# FRU_Programmer.net
KiCad netlist of a schematic drawn in Altium Designer
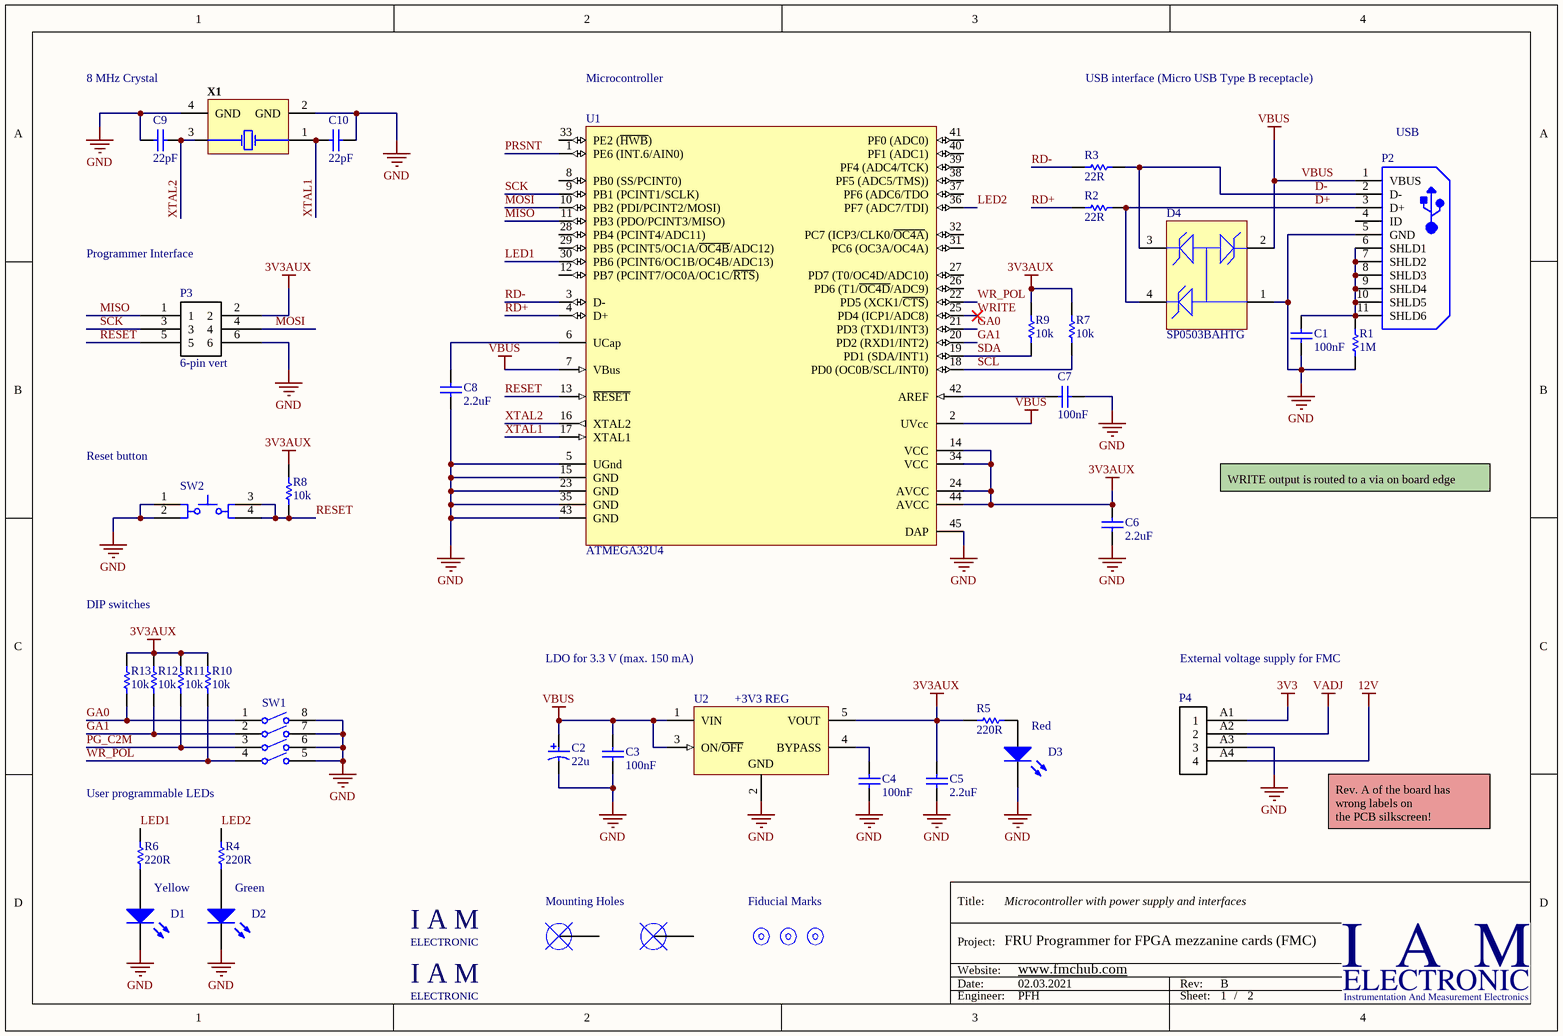
[diagram p0: FRU_Programmer.SchDoc]

(export (version "E")
  (design (tool "Eeschema 10.0.6"))
  (components
    (comp (ref "C1")
      (value "100nF")
      (footprint "CAPC0603(1608)100_L")
      (description "CAP 100nF, 0603 (1608 Metric)")
      (fields (field (name "TOLERANCE") "Â±5%") (field (name "PART") "C0603C104M4RAC7411"))
      (libsource (lib "Altium Content Vault") (part "CAP"))
    )
    (comp (ref "C2")
      (value "22u")
      (footprint "AVX-TAJ-B-2_L")
      (description "Standard Tantalum, 22 uF, +/- 10%, 16 V, -55 to 125 degC, 2-Pin SMD (1210), RoHS, Tape and Reel")
      (fields (field (name "TOLERANCE") "10%") (field (name "MANUFACTURER") "AVX"))
      (libsource (lib "Altium Content Vault") (part "CAP-P-2"))
    )
    (comp (ref "C3")
      (value "100nF")
      (footprint "CAPC0603(1608)100_L")
      (description "CAP 100nF, 0603 (1608 Metric)")
      (fields (field (name "TOLERANCE") "Â±5%") (field (name "PART") "C0603C104M4RAC7411"))
      (libsource (lib "Altium Content Vault") (part "CAP"))
    )
    (comp (ref "C4")
      (value "100nF")
      (footprint "CAPC0603(1608)100_L")
      (description "CAP 100nF, 0603 (1608 Metric)")
      (fields (field (name "TOLERANCE") "Â±5%") (field (name "MANUFACTURER") "KEMET"))
      (libsource (lib "Altium Content Vault") (part "CAP"))
    )
    (comp (ref "C5")
      (value "2.2uF")
      (footprint "CAPC0603(1608)100_L")
      (description "CAP 2.2uF, 0603 (1608 Metric)")
      (fields (field (name "TOLERANCE") "Â±5%") (field (name "PART") "C0603C225K4PACTU"))
      (libsource (lib "Altium Content Vault") (part "CAP"))
    )
    (comp (ref "C6")
      (value "2.2uF")
      (footprint "CAPC0603(1608)100_L")
      (description "CAP 2.2uF, 0603 (1608 Metric)")
      (fields (field (name "TOLERANCE") "Â±5%") (field (name "PART") "C0603C225K4PACTU"))
      (libsource (lib "Altium Content Vault") (part "CAP"))
    )
    (comp (ref "C7")
      (value "100nF")
      (footprint "CAPC0603(1608)100_L")
      (description "CAP 100nF, 0603 (1608 Metric)")
      (fields (field (name "TOLERANCE") "Â±5%") (field (name "PART") "C0603C104M4RAC7411"))
      (libsource (lib "Altium Content Vault") (part "CAP"))
    )
    (comp (ref "C8")
      (value "2.2uF")
      (footprint "CAPC0603(1608)100_L")
      (description "CAP 2.2uF, 0603 (1608 Metric)")
      (fields (field (name "TOLERANCE") "Â±5%") (field (name "MANUFACTURER") "KEMET"))
      (libsource (lib "Altium Content Vault") (part "CAP"))
    )
    (comp (ref "C9")
      (value "22pF")
      (footprint "CAPC0603(1608)100_L")
      (description "CAP 22pF, 0603 (1608 Metric)")
      (fields (field (name "TOLERANCE") "Â±5%") (field (name "PART") "CC0603JRNPO9BN220"))
      (libsource (lib "Altium Content Vault") (part "CAP"))
    )
    (comp (ref "C10")
      (value "22pF")
      (footprint "CAPC0603(1608)100_L")
      (description "CAP 22pF, 0603 (1608 Metric)")
      (fields (field (name "TOLERANCE") "Â±5%") (field (name "PART") "CC0603JRNPO9BN220"))
      (libsource (lib "Altium Content Vault") (part "CAP"))
    )
    (comp (ref "D1")
      (value "LED Yellow")
      (footprint "0603_A")
      (description "LED 0603, 2V, Yellow")
      (fields (field (name "PARTNUMBER") "150060YS75000") (field (name "MANUFACTURER") "Wuerth Elektronik"))
      (libsource (lib "Altium Content Vault") (part "WE-LED_K1A2-2"))
    )
    (comp (ref "D2")
      (value "LED Green")
      (footprint "0603_A")
      (description "LED 0603, 2V, Green")
      (fields (field (name "PARTNUMBER") "150060VS75000") (field (name "MANUFACTURER") "Wuerth Elektronik"))
      (libsource (lib "Altium Content Vault") (part "WE-LED_K1A2-2"))
    )
    (comp (ref "D3")
      (value "LED Red")
      (footprint "0603_A")
      (description "LED 0603, 2V, Red")
      (fields (field (name "PARTNUMBER") "150060RS75000") (field (name "MANUFACTURER") "Wuerth Elektronik"))
      (libsource (lib "Altium Content Vault") (part "WE-LED_K1A2-2"))
    )
    (comp (ref "D4")
      (value "SP0503BAHTG")
      (footprint "LFUS-SOT143-4_V")
      (description "TVS Diode Array, 30 pF, 30 KV, -40 to 85 degC, 4-Pin SOT143, RoHS, Tape and Reel")
      (fields (field (name "MANUFACTURER") "Littelfuse"))
      (libsource (lib "Altium Content Vault") (part "LFUS-SP0503BAHTG-SOT143-4"))
    )
    (comp (ref "FM1")
      (value "1mm")
      (footprint "FIDUCIAL_MARK_ROUND_RING")
      (description "Fiducial mark, width 1mm, clearance 3mm")
      (libsource (lib "VITA_57_FMC") (part "Fiducial_Mark"))
    )
    (comp (ref "FM2")
      (value "1mm")
      (footprint "FIDUCIAL_MARK_ROUND_RING")
      (description "Fiducial mark, width 1mm, clearance 3mm")
      (libsource (lib "VITA_57_FMC") (part "Fiducial_Mark"))
    )
    (comp (ref "FM3")
      (value "1mm")
      (footprint "FIDUCIAL_MARK_ROUND_RING")
      (description "Fiducial mark, width 1mm, clearance 3mm")
      (libsource (lib "VITA_57_FMC") (part "Fiducial_Mark"))
    )
    (comp (ref "MH1")
      (value "2.7mm")
      (footprint "Mounting_Hole_Plated_2.7mm-COVERED")
      (description "Mounting hole, hole size 2.7mm")
      (libsource (lib "VITA_57_FMC") (part "Mounting_Hole_2.7mm"))
    )
    (comp (ref "MH2")
      (value "2.7mm")
      (footprint "Mounting_Hole_Plated_2.7mm-COVERED")
      (description "Mounting hole, hole size 2.7mm")
      (libsource (lib "VITA_57_FMC") (part "Mounting_Hole_2.7mm"))
    )
    (comp (ref "P2")
      (value "USB Jack")
      (footprint "FCI-10118193-0001LF-5_V")
      (description "Micro USB B Type Receptacle, -55 to 85 degC, 5-Pin SMD, RoHS, Tape and Reel")
      (fields (field (name "MANUFACTURER") "FCI") (field (name "PART") "10118193-0001LF"))
      (libsource (lib "Altium Content Vault") (part "USB-5-6SHLD"))
    )
    (comp (ref "P3")
      (value "6-pin vert")
      (footprint "TSM-103-01-T-DV")
      (description ".100\" (2.54 mm) pitch 6 pin (dual row) header, 0.38\" (9.65 mm) total height, SMT")
      (fields (field (name "MANUFACTURER") "Samtec") (field (name "PART") "TSM-103-01-T-DV"))
      (libsource (lib "SMTC-TSM") (part "TSM-103-01-T-DV"))
    )
    (comp (ref "P4")
      (value "PTSM SMT connector")
      (footprint "PTSM-4pol")
      (description "Phoenix Contact PTSM SMT connector")
      (fields (field (name "MANUFACTURER") "Phoenix Contact") (field (name "PART") "1814650"))
      (libsource (lib "PC-PTSM") (part "PC-PTSM-4pol"))
    )
    (comp (ref "R1")
      (value "1M")
      (footprint "RESC1608X55X25NL10T15")
      (description "Resistor, 1 MOhm, 0603 (1608 Metric)")
      (fields (field (name "MANUFACTURER") "Yageo") (field (name "TOLERANCE") "5%"))
      (libsource (lib "Altium Content Vault") (part "RES-2"))
    )
    (comp (ref "R2")
      (value "22R")
      (footprint "RESC0603(1608)_L")
      (description "22R 0.1W 5% 0603 (1608 Metric)  SMD")
      (fields (field (name "POWER") "0.1 W") (field (name "TOLERANCE") "5 %"))
      (libsource (lib "Altium Content Vault") (part "CMP-1012-00034-1"))
    )
    (comp (ref "R3")
      (value "22R")
      (footprint "RESC0603(1608)_L")
      (description "22R 0.1W 5% 0603 (1608 Metric)  SMD")
      (fields (field (name "POWER") "0.1 W") (field (name "TOLERANCE") "5 %"))
      (libsource (lib "Altium Content Vault") (part "CMP-1012-00034-1"))
    )
    (comp (ref "R4")
      (value "220R")
      (footprint "RESC1608X55X25NL10T15")
      (description "Resistors, 220 Ohm, +/- 1%, 0603 (1608 Metric)")
      (fields (field (name "PART") "RC0603FR-07220RL") (field (name "MANUFACTURER") "Yageo"))
      (libsource (lib "Altium Content Vault") (part "RES-2"))
    )
    (comp (ref "R5")
      (value "220R")
      (footprint "RESC1608X55X25NL10T15")
      (description "Resistors, 220 Ohm, +/- 1%, 0603 (1608 Metric)")
      (fields (field (name "PART") "RC0603FR-07220RL") (field (name "MANUFACTURER") "Yageo"))
      (libsource (lib "Altium Content Vault") (part "RES-2"))
    )
    (comp (ref "R6")
      (value "220R")
      (footprint "RESC1608X55X25NL10T15")
      (description "Resistors, 220 Ohm, +/- 1%, 0603 (1608 Metric)")
      (fields (field (name "PART") "RC0603FR-07220RL") (field (name "MANUFACTURER") "Yageo"))
      (libsource (lib "Altium Content Vault") (part "RES-2"))
    )
    (comp (ref "R7")
      (value "10k")
      (footprint "RESC1608X55X25NL10T15")
      (description "Resistor, 10 KOhm, 0603 (1608 Metric)")
      (fields (field (name "MANUFACTURER") "Walsin") (field (name "TOLERANCE") "5%"))
      (libsource (lib "Altium Content Vault") (part "RES-2"))
    )
    (comp (ref "R8")
      (value "10k")
      (footprint "RESC1608X55X25NL10T15")
      (description "Resistor, 10 KOhm, 0603 (1608 Metric)")
      (fields (field (name "MANUFACTURER") "Walsin") (field (name "TOLERANCE") "5%"))
      (libsource (lib "Altium Content Vault") (part "RES-2"))
    )
    (comp (ref "R9")
      (value "10k")
      (footprint "RESC1608X55X25NL10T15")
      (description "Resistor, 10 KOhm, 0603 (1608 Metric)")
      (fields (field (name "MANUFACTURER") "Walsin") (field (name "TOLERANCE") "5%"))
      (libsource (lib "Altium Content Vault") (part "RES-2"))
    )
    (comp (ref "R10")
      (value "10k")
      (footprint "RESC1608X55X25NL10T15")
      (description "Resistor, 10 KOhm, 0603 (1608 Metric)")
      (fields (field (name "MANUFACTURER") "Walsin") (field (name "TOLERANCE") "5%"))
      (libsource (lib "Altium Content Vault") (part "RES-2"))
    )
    (comp (ref "R11")
      (value "10k")
      (footprint "RESC1608X55X25NL10T15")
      (description "Resistor, 10 KOhm, 0603 (1608 Metric)")
      (fields (field (name "MANUFACTURER") "Walsin") (field (name "TOLERANCE") "5%"))
      (libsource (lib "Altium Content Vault") (part "RES-2"))
    )
    (comp (ref "R12")
      (value "10k")
      (footprint "RESC1608X55X25NL10T15")
      (description "Resistor, 10 KOhm, 0603 (1608 Metric)")
      (fields (field (name "MANUFACTURER") "Walsin") (field (name "TOLERANCE") "5%"))
      (libsource (lib "Altium Content Vault") (part "RES-2"))
    )
    (comp (ref "R13")
      (value "10k")
      (footprint "RESC1608X55X25NL10T15")
      (description "Resistor, 10 KOhm, 0603 (1608 Metric)")
      (fields (field (name "MANUFACTURER") "Walsin") (field (name "TOLERANCE") "5%"))
      (libsource (lib "Altium Content Vault") (part "RES-2"))
    )
    (comp (ref "STR1")
      (value "IAM LOGO")
      (footprint "IAM LOGO - MEDIUM - WWW")
      (description "I A M E L E C T R O N I C - Logo")
      (fields (field (name "MANUFACTURER") "IAM ELECTRONIC") (field (name "PART") "Logo"))
      (libsource (lib "IAM_LOGOS") (part "IAM_LOGO"))
    )
    (comp (ref "STR2")
      (value "IAM LOGO")
      (footprint "IAM LOGO - LARGE - WWW")
      (description "I A M E L E C T R O N I C - Logo")
      (fields (field (name "MANUFACTURER") "IAM ELECTRONIC") (field (name "PART") "Logo"))
      (libsource (lib "IAM_LOGOS") (part "IAM_LOGO"))
    )
    (comp (ref "SW1")
      (value "DIP switch")
      (footprint "218-4LPST")
      (description "4 channel DIP switch")
      (fields (field (name "MANUFACTURER") "CTS Electronic Components") (field (name "PART") "218-4LPST"))
      (libsource (lib "CTS-218") (part "218-4LPST"))
    )
    (comp (ref "SW2")
      (value "Push switch")
      (footprint "ESWI-TL3342F160QG_V")
      (description "Switch, Tactile, SPST-NO, 50 mA, 12 V, 4-Pin SMD, RoHS, Tape and Reel")
      (fields (field (name "TOLERANCE") "20%") (field (name "PART") "TL3342F160QG"))
      (libsource (lib "Altium Content Vault") (part "SW-SPST-NO-4"))
    )
    (comp (ref "U1")
      (value "ATMEGA32U4")
      (footprint "44PW_M")
      (fields (field (name "PART") "ATMEGA32U4-MU") (field (name "MANUFACTURER") "Microchip"))
      (libsource (lib "Altium Content Vault") (part "MC-8B-ATM16U4-SQ45"))
    )
    (comp (ref "U2")
      (value "LP2985-33")
      (footprint "DBV0005A_M")
      (fields (field (name "MANUFACTURER") "Texas Instruments") (field (name "PARTNUMBER") "LP2985-33DBVR"))
      (libsource (lib "Altium Content Vault") (part "TI-LP2985_A-10DBV5"))
    )
    (comp (ref "X1")
      (value "8 MHz")
      (footprint "ABRA-ABM3B_V")
      (description "Ceramic Crystal, 8 MHz, +/- 10 ppm, -10 to 60 degC, 4-Pin SMD, RoHS, Tape and Reel")
      (fields (field (name "MANUFACTURER") "Abracon-LLC") (field (name "PART") "ABM3B-8.000MHZ-10-1-U-T"))
      (libsource (lib "Altium Content Vault") (part "XTAL-1-3-4"))
    )
  )
  (nets
    (net (code "1") (name "/D+") (class "Default")
      (node (ref "D4") (pin "4") (pinfunction "4_4") (pintype "passive"))
      (node (ref "P2") (pin "3") (pinfunction "D+_3") (pintype "passive"))
      (node (ref "R2") (pin "2") (pinfunction "2_2") (pintype "passive"))
    )
    (net (code "2") (name "/D-") (class "Default")
      (node (ref "D4") (pin "3") (pinfunction "3_3") (pintype "passive"))
      (node (ref "P2") (pin "2") (pinfunction "D-_2") (pintype "passive"))
      (node (ref "R3") (pin "2") (pinfunction "2_2") (pintype "passive"))
    )
    (net (code "3") (name "/GA0") (class "Default")
      (node (ref "R13") (pin "2") (pinfunction "2_2") (pintype "passive"))
      (node (ref "SW1") (pin "1") (pinfunction "1_1") (pintype "passive"))
      (node (ref "U1") (pin "21") (pinfunction "PD3_(TXD1/INT3)_21") (pintype "bidirectional"))
    )
    (net (code "4") (name "/GA1") (class "Default")
      (node (ref "R12") (pin "2") (pinfunction "2_2") (pintype "passive"))
      (node (ref "SW1") (pin "2") (pinfunction "2_2") (pintype "passive"))
      (node (ref "U1") (pin "20") (pinfunction "PD2_(RXD1/INT2)_20") (pintype "bidirectional"))
    )
    (net (code "5") (name "/LED1") (class "Default")
      (node (ref "R6") (pin "2") (pinfunction "2_2") (pintype "passive"))
      (node (ref "U1") (pin "30") (pinfunction "PB6_(PCINT6/OC1B/OC4B/ADC13)_30") (pintype "bidirectional"))
    )
    (net (code "6") (name "/LED2") (class "Default")
      (node (ref "R4") (pin "2") (pinfunction "2_2") (pintype "passive"))
      (node (ref "U1") (pin "36") (pinfunction "PF7_(ADC7/TDI)_36") (pintype "bidirectional"))
    )
    (net (code "7") (name "/MISO") (class "Default")
      (node (ref "P3") (pin "1") (pinfunction "1_1") (pintype "passive"))
      (node (ref "U1") (pin "11") (pinfunction "PB3_(PDO/PCINT3/MISO)_11") (pintype "bidirectional"))
    )
    (net (code "8") (name "/MOSI") (class "Default")
      (node (ref "P3") (pin "4") (pinfunction "4_4") (pintype "passive"))
      (node (ref "U1") (pin "10") (pinfunction "PB2_(PDI/PCINT2/MOSI)_10") (pintype "bidirectional"))
    )
    (net (code "9") (name "/PG_C2M") (class "Default")
      (node (ref "R11") (pin "2") (pinfunction "2_2") (pintype "passive"))
      (node (ref "SW1") (pin "3") (pinfunction "3_3") (pintype "passive"))
    )
    (net (code "10") (name "/PRSNT") (class "Default")
      (node (ref "U1") (pin "1") (pinfunction "PE6_(INT.6/AIN0)_1") (pintype "bidirectional"))
    )
    (net (code "11") (name "/RD+") (class "Default")
      (node (ref "R2") (pin "1") (pinfunction "1_1") (pintype "passive"))
      (node (ref "U1") (pin "4") (pinfunction "D+_4") (pintype "bidirectional"))
    )
    (net (code "12") (name "/RD-") (class "Default")
      (node (ref "R3") (pin "1") (pinfunction "1_1") (pintype "passive"))
      (node (ref "U1") (pin "3") (pinfunction "D-_3") (pintype "bidirectional"))
    )
    (net (code "13") (name "/RESET") (class "Default")
      (node (ref "P3") (pin "5") (pinfunction "5_5") (pintype "passive"))
      (node (ref "R8") (pin "2") (pinfunction "2_2") (pintype "passive"))
      (node (ref "SW2") (pin "3") (pinfunction "3_3") (pintype "passive"))
      (node (ref "SW2") (pin "4") (pinfunction "4_4") (pintype "passive"))
      (node (ref "U1") (pin "13") (pinfunction "~{RESET}_13") (pintype "input"))
    )
    (net (code "14") (name "/SCK") (class "Default")
      (node (ref "P3") (pin "3") (pinfunction "3_3") (pintype "passive"))
      (node (ref "U1") (pin "9") (pinfunction "PB1_(PCINT1/SCLK)_9") (pintype "bidirectional"))
    )
    (net (code "15") (name "/SCL") (class "Default")
      (node (ref "R7") (pin "1") (pinfunction "1_1") (pintype "passive"))
      (node (ref "U1") (pin "18") (pinfunction "PD0_(OC0B/SCL/INT0)_18") (pintype "bidirectional"))
    )
    (net (code "16") (name "/SDA") (class "Default")
      (node (ref "R9") (pin "1") (pinfunction "1_1") (pintype "passive"))
      (node (ref "U1") (pin "19") (pinfunction "PD1_(SDA/INT1)_19") (pintype "bidirectional"))
    )
    (net (code "17") (name "/WRITE") (class "Default")
      (node (ref "U1") (pin "25") (pinfunction "PD4_(ICP1/ADC8)_25") (pintype "bidirectional+no_connect"))
    )
    (net (code "18") (name "/WR_POL") (class "Default")
      (node (ref "R10") (pin "2") (pinfunction "2_2") (pintype "passive"))
      (node (ref "SW1") (pin "4") (pinfunction "4_4") (pintype "passive"))
      (node (ref "U1") (pin "22") (pinfunction "PD5_(XCK1/~{CTS})_22") (pintype "bidirectional"))
    )
    (net (code "19") (name "/XTAL1") (class "Default")
      (node (ref "C10") (pin "1") (pinfunction "1_1") (pintype "passive"))
      (node (ref "U1") (pin "17") (pinfunction "XTAL1_17") (pintype "input"))
      (node (ref "X1") (pin "1") (pinfunction "X1_1") (pintype "passive"))
    )
    (net (code "20") (name "/XTAL2") (class "Default")
      (node (ref "C9") (pin "2") (pinfunction "2_2") (pintype "passive"))
      (node (ref "U1") (pin "16") (pinfunction "XTAL2_16") (pintype "output"))
      (node (ref "X1") (pin "3") (pinfunction "X2_3") (pintype "passive"))
    )
    (net (code "21") (name "3V3") (class "Default")
      (node (ref "P4") (pin "A1") (pinfunction "1_A1") (pintype "passive"))
    )
    (net (code "22") (name "3V3AUX") (class "Default")
      (node (ref "C5") (pin "1") (pinfunction "1_1") (pintype "passive"))
      (node (ref "C6") (pin "1") (pinfunction "1_1") (pintype "passive"))
      (node (ref "P3") (pin "2") (pinfunction "2_2") (pintype "passive"))
      (node (ref "R10") (pin "1") (pinfunction "1_1") (pintype "passive"))
      (node (ref "R11") (pin "1") (pinfunction "1_1") (pintype "passive"))
      (node (ref "R12") (pin "1") (pinfunction "1_1") (pintype "passive"))
      (node (ref "R13") (pin "1") (pinfunction "1_1") (pintype "passive"))
      (node (ref "R5") (pin "2") (pinfunction "2_2") (pintype "passive"))
      (node (ref "R7") (pin "2") (pinfunction "2_2") (pintype "passive"))
      (node (ref "R8") (pin "1") (pinfunction "1_1") (pintype "passive"))
      (node (ref "R9") (pin "2") (pinfunction "2_2") (pintype "passive"))
      (node (ref "U1") (pin "14") (pinfunction "VCC_14") (pintype "power_in"))
      (node (ref "U1") (pin "24") (pinfunction "AVCC_24") (pintype "power_in"))
      (node (ref "U1") (pin "34") (pinfunction "VCC_34") (pintype "power_in"))
      (node (ref "U1") (pin "44") (pinfunction "AVCC_44") (pintype "power_in"))
      (node (ref "U2") (pin "5") (pinfunction "VOUT_5") (pintype "power_in"))
    )
    (net (code "23") (name "12V") (class "Default")
      (node (ref "P4") (pin "A4") (pinfunction "4_A4") (pintype "passive"))
    )
    (net (code "24") (name "GND") (class "Default")
      (node (ref "C1") (pin "2") (pinfunction "2_2") (pintype "passive"))
      (node (ref "C10") (pin "2") (pinfunction "2_2") (pintype "passive"))
      (node (ref "C2") (pin "2") (pinfunction "2_2") (pintype "passive"))
      (node (ref "C3") (pin "2") (pinfunction "2_2") (pintype "passive"))
      (node (ref "C4") (pin "2") (pinfunction "2_2") (pintype "passive"))
      (node (ref "C5") (pin "2") (pinfunction "2_2") (pintype "passive"))
      (node (ref "C6") (pin "2") (pinfunction "2_2") (pintype "passive"))
      (node (ref "C7") (pin "2") (pinfunction "2_2") (pintype "passive"))
      (node (ref "C8") (pin "2") (pinfunction "2_2") (pintype "passive"))
      (node (ref "C9") (pin "1") (pinfunction "1_1") (pintype "passive"))
      (node (ref "D1") (pin "1") (pinfunction "K_1") (pintype "passive"))
      (node (ref "D2") (pin "1") (pinfunction "K_1") (pintype "passive"))
      (node (ref "D3") (pin "1") (pinfunction "K_1") (pintype "passive"))
      (node (ref "D4") (pin "1") (pinfunction "1_1") (pintype "passive"))
      (node (ref "P2") (pin "5") (pinfunction "GND_5") (pintype "passive"))
      (node (ref "P3") (pin "6") (pinfunction "6_6") (pintype "passive"))
      (node (ref "P4") (pin "A3") (pinfunction "3_A3") (pintype "passive"))
      (node (ref "R1") (pin "1") (pinfunction "1_1") (pintype "passive"))
      (node (ref "SW1") (pin "5") (pinfunction "5_5") (pintype "passive"))
      (node (ref "SW1") (pin "6") (pinfunction "6_6") (pintype "passive"))
      (node (ref "SW1") (pin "7") (pinfunction "7_7") (pintype "passive"))
      (node (ref "SW1") (pin "8") (pinfunction "8_8") (pintype "passive"))
      (node (ref "SW2") (pin "1") (pinfunction "1_1") (pintype "passive"))
      (node (ref "SW2") (pin "2") (pinfunction "2_2") (pintype "passive"))
      (node (ref "U1") (pin "15") (pinfunction "GND_15") (pintype "power_in"))
      (node (ref "U1") (pin "23") (pinfunction "GND_23") (pintype "power_in"))
      (node (ref "U1") (pin "35") (pinfunction "GND_35") (pintype "power_in"))
      (node (ref "U1") (pin "43") (pinfunction "GND_43") (pintype "power_in"))
      (node (ref "U1") (pin "45") (pinfunction "DAP_45") (pintype "power_in"))
      (node (ref "U1") (pin "5") (pinfunction "UGnd_5") (pintype "power_in"))
      (node (ref "U2") (pin "2") (pinfunction "GND_2") (pintype "power_in"))
      (node (ref "X1") (pin "2") (pinfunction "GND_2") (pintype "power_in"))
      (node (ref "X1") (pin "4") (pinfunction "GND_4") (pintype "power_in"))
    )
    (net (code "25") (name "Net-(D1-A)") (class "Default")
      (node (ref "D1") (pin "2") (pinfunction "A_2") (pintype "passive"))
      (node (ref "R6") (pin "1") (pinfunction "1_1") (pintype "passive"))
    )
    (net (code "26") (name "Net-(D2-A)") (class "Default")
      (node (ref "D2") (pin "2") (pinfunction "A_2") (pintype "passive"))
      (node (ref "R4") (pin "1") (pinfunction "1_1") (pintype "passive"))
    )
    (net (code "27") (name "Net-(D3-A)") (class "Default")
      (node (ref "D3") (pin "2") (pinfunction "A_2") (pintype "passive"))
      (node (ref "R5") (pin "1") (pinfunction "1_1") (pintype "passive"))
    )
    (net (code "28") (name "Net-(P2-SHLD1)") (class "Default")
      (node (ref "C1") (pin "1") (pinfunction "1_1") (pintype "passive"))
      (node (ref "P2") (pin "10") (pinfunction "SHLD5_10") (pintype "passive"))
      (node (ref "P2") (pin "11") (pinfunction "SHLD6_11") (pintype "passive"))
      (node (ref "P2") (pin "6") (pinfunction "SHLD1_6") (pintype "passive"))
      (node (ref "P2") (pin "7") (pinfunction "SHLD2_7") (pintype "passive"))
      (node (ref "P2") (pin "8") (pinfunction "SHLD3_8") (pintype "passive"))
      (node (ref "P2") (pin "9") (pinfunction "SHLD4_9") (pintype "passive"))
      (node (ref "R1") (pin "2") (pinfunction "2_2") (pintype "passive"))
    )
    (net (code "29") (name "Net-(U1-AREF)") (class "Default")
      (node (ref "C7") (pin "1") (pinfunction "1_1") (pintype "passive"))
      (node (ref "U1") (pin "42") (pinfunction "AREF_42") (pintype "input"))
    )
    (net (code "30") (name "Net-(U1-UCap)") (class "Default")
      (node (ref "C8") (pin "1") (pinfunction "1_1") (pintype "passive"))
      (node (ref "U1") (pin "6") (pinfunction "UCap_6") (pintype "passive"))
    )
    (net (code "31") (name "Net-(U2-BYPASS)") (class "Default")
      (node (ref "C4") (pin "1") (pinfunction "1_1") (pintype "passive"))
      (node (ref "U2") (pin "4") (pinfunction "BYPASS_4") (pintype "passive"))
    )
    (net (code "32") (name "VADJ") (class "Default")
      (node (ref "P4") (pin "A2") (pinfunction "2_A2") (pintype "passive"))
    )
    (net (code "33") (name "VBUS") (class "Default")
      (node (ref "C2") (pin "1") (pinfunction "1_1") (pintype "passive"))
      (node (ref "C3") (pin "1") (pinfunction "1_1") (pintype "passive"))
      (node (ref "D4") (pin "2") (pinfunction "2_2") (pintype "passive"))
      (node (ref "P2") (pin "1") (pinfunction "VBUS_1") (pintype "passive"))
      (node (ref "U1") (pin "2") (pinfunction "UVcc_2") (pintype "power_in"))
      (node (ref "U1") (pin "7") (pinfunction "VBus_7") (pintype "input"))
      (node (ref "U2") (pin "1") (pinfunction "VIN_1") (pintype "power_in"))
      (node (ref "U2") (pin "3") (pinfunction "ON/~{OFF}_3") (pintype "input"))
    )
    (net (code "34") (name "unconnected-(FM1-PadFD0)") (class "Default")
      (node (ref "FM1") (pin "FD0") (pinfunction "FD0_FD0") (pintype "passive"))
    )
    (net (code "35") (name "unconnected-(FM2-PadFD0)") (class "Default")
      (node (ref "FM2") (pin "FD0") (pinfunction "FD0_FD0") (pintype "passive"))
    )
    (net (code "36") (name "unconnected-(FM3-PadFD0)") (class "Default")
      (node (ref "FM3") (pin "FD0") (pinfunction "FD0_FD0") (pintype "passive"))
    )
    (net (code "37") (name "unconnected-(MH1-Pad0)") (class "Default")
      (node (ref "MH1") (pin "0") (pinfunction "0_0") (pintype "passive"))
    )
    (net (code "38") (name "unconnected-(MH2-Pad0)") (class "Default")
      (node (ref "MH2") (pin "0") (pinfunction "0_0") (pintype "passive"))
    )
    (net (code "39") (name "unconnected-(P2-ID-Pad4)") (class "Default")
      (node (ref "P2") (pin "4") (pinfunction "ID_4") (pintype "passive"))
    )
    (net (code "40") (name "unconnected-(U1-PB0_(SS{slash}PCINT0)-Pad8)") (class "Default")
      (node (ref "U1") (pin "8") (pinfunction "PB0_(SS/PCINT0)_8") (pintype "bidirectional"))
    )
    (net (code "41") (name "unconnected-(U1-PB4_(PCINT4{slash}ADC11)-Pad28)") (class "Default")
      (node (ref "U1") (pin "28") (pinfunction "PB4_(PCINT4/ADC11)_28") (pintype "bidirectional"))
    )
    (net (code "42") (name "unconnected-(U1-PB5_(PCINT5{slash}OC1A{slash}~{OC4B}{slash}ADC12)-Pad29)") (class "Default")
      (node (ref "U1") (pin "29") (pinfunction "PB5_(PCINT5/OC1A/~{OC4B}/ADC12)_29") (pintype "bidirectional"))
    )
    (net (code "43") (name "unconnected-(U1-PB7_(PCINT7{slash}OC0A{slash}OC1C{slash}~{RTS})-Pad12)") (class "Default")
      (node (ref "U1") (pin "12") (pinfunction "PB7_(PCINT7/OC0A/OC1C/~{RTS})_12") (pintype "bidirectional"))
    )
    (net (code "44") (name "unconnected-(U1-PC6_(OC3A{slash}OC4A)-Pad31)") (class "Default")
      (node (ref "U1") (pin "31") (pinfunction "PC6_(OC3A/OC4A)_31") (pintype "bidirectional"))
    )
    (net (code "45") (name "unconnected-(U1-PC7_(ICP3{slash}CLK0{slash}~{OC4A})-Pad32)") (class "Default")
      (node (ref "U1") (pin "32") (pinfunction "PC7_(ICP3/CLK0/~{OC4A})_32") (pintype "bidirectional"))
    )
    (net (code "46") (name "unconnected-(U1-PD6_(T1{slash}~{OC4D}{slash}ADC9)-Pad26)") (class "Default")
      (node (ref "U1") (pin "26") (pinfunction "PD6_(T1/~{OC4D}/ADC9)_26") (pintype "bidirectional"))
    )
    (net (code "47") (name "unconnected-(U1-PD7_(T0{slash}OC4D{slash}ADC10)-Pad27)") (class "Default")
      (node (ref "U1") (pin "27") (pinfunction "PD7_(T0/OC4D/ADC10)_27") (pintype "bidirectional"))
    )
    (net (code "48") (name "unconnected-(U1-PE2_(~{HWB})-Pad33)") (class "Default")
      (node (ref "U1") (pin "33") (pinfunction "PE2_(~{HWB})_33") (pintype "bidirectional"))
    )
    (net (code "49") (name "unconnected-(U1-PF0_(ADC0)-Pad41)") (class "Default")
      (node (ref "U1") (pin "41") (pinfunction "PF0_(ADC0)_41") (pintype "bidirectional"))
    )
    (net (code "50") (name "unconnected-(U1-PF1_(ADC1)-Pad40)") (class "Default")
      (node (ref "U1") (pin "40") (pinfunction "PF1_(ADC1)_40") (pintype "bidirectional"))
    )
    (net (code "51") (name "unconnected-(U1-PF4_(ADC4{slash}TCK)-Pad39)") (class "Default")
      (node (ref "U1") (pin "39") (pinfunction "PF4_(ADC4/TCK)_39") (pintype "bidirectional"))
    )
    (net (code "52") (name "unconnected-(U1-PF5_(ADC5{slash}TMS))-Pad38)") (class "Default")
      (node (ref "U1") (pin "38") (pinfunction "PF5_(ADC5/TMS))_38") (pintype "bidirectional"))
    )
    (net (code "53") (name "unconnected-(U1-PF6_(ADC6{slash}TDO-Pad37)") (class "Default")
      (node (ref "U1") (pin "37") (pinfunction "PF6_(ADC6/TDO_37") (pintype "bidirectional"))
    )
  )
)
